# Battery_Management.net
KiCad netlist of a schematic drawn in Altium Designer
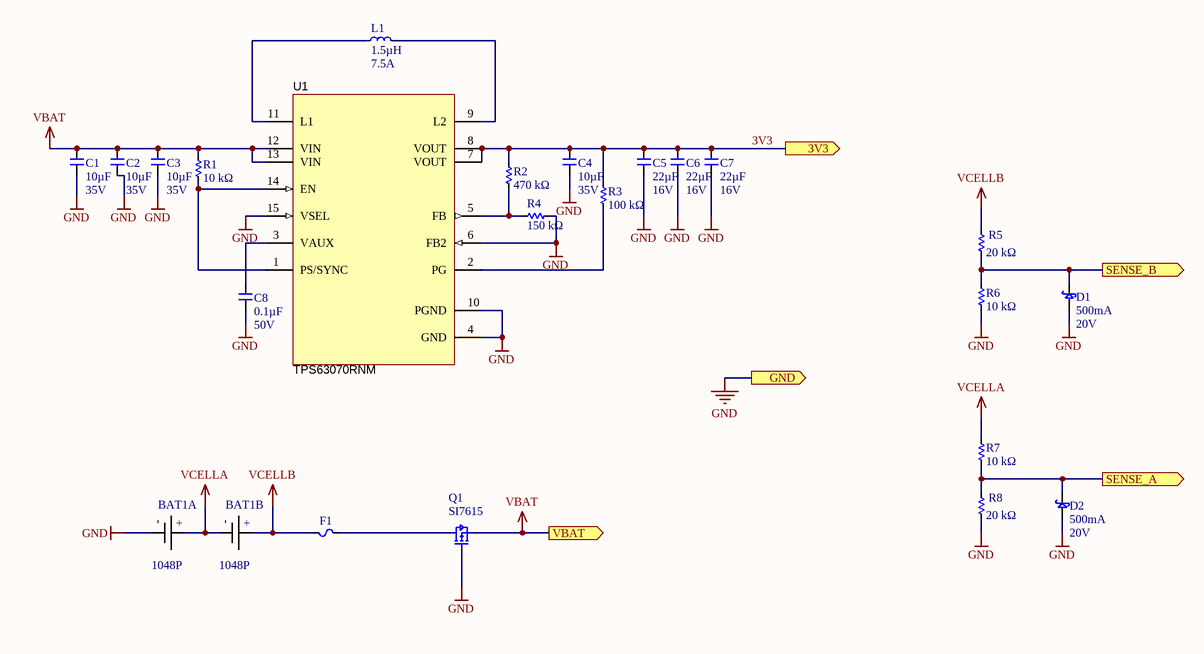
[diagram p0: Battery_Management.SchDoc]

(export (version "E")
  (design (tool "Eeschema 10.0.6"))
  (components
    (comp (ref "BAT1")
      (value "BATT_Clip_Li-Ion_2x")
      (footprint "BATT_18650_KEYSTONE_1048")
      (description "Dual Lithium Ion Cell Holder")
      (fields
        (field (name "MANUFACTURER PART NUMBER") "1048P")
        (field (name "MANUFACTURER") "Keystone Electronics")
      )
      (libsource (lib "Stanford Student Space Initiative") (part "BATT_Clip_Li-Ion_2x"))
    )
    (comp (ref "C1")
      (value "490-13248-1-ND")
      (footprint "C0603")
      (description "CAP CER 10UF 35V X5R 0603 20%")
      (fields
        (field (name "CAPACITANCE (SHORTHAND)") "10µF")
        (field (name "RATED VOLTAGE") "35V")
        (field (name "MANUFACTURER") "Murata Electronics North America")
      )
      (libsource (lib "Stanford Student Space Initiative") (part "__template_cap"))
    )
    (comp (ref "C2")
      (value "490-13248-1-ND")
      (footprint "C0603")
      (description "CAP CER 10UF 35V X5R 0603 20%")
      (fields
        (field (name "CAPACITANCE (SHORTHAND)") "10µF")
        (field (name "RATED VOLTAGE") "35V")
        (field (name "MANUFACTURER") "Murata Electronics North America")
      )
      (libsource (lib "Stanford Student Space Initiative") (part "__template_cap"))
    )
    (comp (ref "C3")
      (value "490-13248-1-ND")
      (footprint "C0603")
      (description "CAP CER 10UF 35V X5R 0603 20%")
      (fields
        (field (name "CAPACITANCE (SHORTHAND)") "10µF")
        (field (name "RATED VOLTAGE") "35V")
        (field (name "MANUFACTURER") "Murata Electronics North America")
      )
      (libsource (lib "Stanford Student Space Initiative") (part "__template_cap"))
    )
    (comp (ref "C4")
      (value "490-13248-1-ND")
      (footprint "C0603")
      (description "CAP CER 10UF 35V X5R 0603 20%")
      (fields
        (field (name "CAPACITANCE (SHORTHAND)") "10µF")
        (field (name "RATED VOLTAGE") "35V")
        (field (name "MANUFACTURER") "Murata Electronics North America")
      )
      (libsource (lib "Stanford Student Space Initiative") (part "__template_cap"))
    )
    (comp (ref "C5")
      (value "1276-7076-1-ND")
      (footprint "C0603")
      (description "CAP CER 22UF 16V X5R 0603 20%")
      (fields
        (field (name "CAPACITANCE (SHORTHAND)") "22µF")
        (field (name "RATED VOLTAGE") "16V")
        (field (name "MANUFACTURER") "Samsung Electro-Mechanics")
      )
      (libsource (lib "Stanford Student Space Initiative") (part "__template_cap"))
    )
    (comp (ref "C6")
      (value "1276-7076-1-ND")
      (footprint "C0603")
      (description "CAP CER 22UF 16V X5R 0603 20%")
      (fields
        (field (name "CAPACITANCE (SHORTHAND)") "22µF")
        (field (name "RATED VOLTAGE") "16V")
        (field (name "MANUFACTURER") "Samsung Electro-Mechanics")
      )
      (libsource (lib "Stanford Student Space Initiative") (part "__template_cap"))
    )
    (comp (ref "C7")
      (value "1276-7076-1-ND")
      (footprint "C0603")
      (description "CAP CER 22UF 16V X5R 0603 20%")
      (fields
        (field (name "CAPACITANCE (SHORTHAND)") "22µF")
        (field (name "RATED VOLTAGE") "16V")
        (field (name "MANUFACTURER") "Samsung Electro-Mechanics")
      )
      (libsource (lib "Stanford Student Space Initiative") (part "__template_cap"))
    )
    (comp (ref "C8")
      (value "490-1519-1-ND")
      (footprint "C0603")
      (description "CAP CER 0603 0.1µF X7R 50V 10%")
      (fields
        (field (name "CAPACITANCE (SHORTHAND)") "0.1µF")
        (field (name "RATED VOLTAGE") "50V")
        (field (name "MANUFACTURER") "Murata Electronics North America")
      )
      (libsource (lib "Stanford Student Space Initiative") (part "__template_cap"))
    )
    (comp (ref "D1")
      (value "SCHOTTKY_MBR0520L")
      (footprint "SOD123")
      (description "DIODE SCHOTTKY 0.5A 20V SOD-123")
      (fields
        (field (name "MANUFACTURER") "Fairchild Semiconductor")
        (field (name "MANUFACTURER PART NUMBER") "MBR0520L")
        (field (name "CURRENT - AVERAGE RECTIFIED (IO)") "500mA")
        (field (name "VOLTAGE - DC REVERSE (VR) (MAX)") "20V")
      )
      (libsource (lib "") (part "Symbol_1"))
    )
    (comp (ref "D2")
      (value "SCHOTTKY_MBR0520L")
      (footprint "SOD123")
      (description "DIODE SCHOTTKY 0.5A 20V SOD-123")
      (fields
        (field (name "MANUFACTURER") "Fairchild Semiconductor")
        (field (name "MANUFACTURER PART NUMBER") "MBR0520L")
        (field (name "CURRENT - AVERAGE RECTIFIED (IO)") "500mA")
        (field (name "VOLTAGE - DC REVERSE (VR) (MAX)") "20V")
      )
      (libsource (lib "") (part "Symbol_1"))
    )
    (comp (ref "F1") (value "__template_fuse") (footprint "R1206") (libsource (lib "") (part "Symbol_2")))
    (comp (ref "L1")
      (value "Symbol")
      (footprint "SMD5230")
      (description "INDUCTOR POWER 1.5UH 7.5A SMD")
      (fields
        (field (name "MANUFACTURER") "Vishay Dale")
        (field (name "MANUFACTURER PART NUMBER") "IHLP2020CZER1R5M11")
        (field (name "INDUCTANCE") "1.5µH")
        (field (name "CURRENT RATING") "7.5A")
      )
      (libsource (lib "Stanford Student Space Initiative") (part "Symbol"))
    )
    (comp (ref "Q1")
      (value "SI7615")
      (footprint "POWERPAK_1212-8_SINGLE")
      (description "MOSFET P-CH 20V 35A PPK")
      (fields
        (field (name "MANUFACTURER") "Vishay Siliconix")
        (field (name "MANUFACTURER PART NUMBER") "SI7615ADN-T1-GE3")
      )
      (libsource (lib "Stanford Student Space Initiative") (part "PFET_SI7615ADN-T1"))
    )
    (comp (ref "R1")
      (value "311-10.0KHRCT-ND")
      (footprint "R0603")
      (description "RES SMD 10K OHM 1% 1/10W 0603")
      (fields
        (field (name "RESISTANCE") "10 kΩ")
        (field (name "MANUFACTURER PART NUMBER") "RC0603FR-0710KL")
        (field (name "MANUFACTURER") "Yageo")
      )
      (libsource (lib "Stanford Student Space Initiative") (part "__template_resistor"))
    )
    (comp (ref "R2")
      (value "311-470KHRCT-ND")
      (footprint "R0603")
      (description "RES SMD 470K OHM 1% 1/10W 0603")
      (fields
        (field (name "MANUFACTURER PART NUMBER") "RC0603FR-07470KL")
        (field (name "MANUFACTURER") "Yageo")
        (field (name "RESISTANCE") "470 kΩ")
      )
      (libsource (lib "Stanford Student Space Initiative") (part "__template_resistor"))
    )
    (comp (ref "R3")
      (value "311-100KHRCT-ND")
      (footprint "R0603")
      (description "RES SMD 100K OHM 1% 1/10W 0603")
      (fields
        (field (name "MANUFACTURER PART NUMBER") "RC0603FR-07100KL")
        (field (name "MANUFACTURER") "Yageo")
        (field (name "RESISTANCE") "100 kΩ")
      )
      (libsource (lib "Stanford Student Space Initiative") (part "__template_resistor"))
    )
    (comp (ref "R4")
      (value "311-150KHRCT-ND")
      (footprint "R0603")
      (description "RES SMD 150K OHM 1% 1/10W 0603")
      (fields
        (field (name "MANUFACTURER PART NUMBER") "RC0603FR-07150KL")
        (field (name "MANUFACTURER") "Yageo")
        (field (name "RESISTANCE") "150 kΩ")
      )
      (libsource (lib "Stanford Student Space Initiative") (part "__template_resistor"))
    )
    (comp (ref "R5")
      (value "311-20.0KHRCT-ND")
      (footprint "R0603")
      (description "RES SMD 20K OHM 1% 1/10W 0603")
      (fields
        (field (name "RESISTANCE") "20 kΩ")
        (field (name "MANUFACTURER PART NUMBER") "RC0603FR-0720KL")
        (field (name "MANUFACTURER") "Yageo")
      )
      (libsource (lib "Stanford Student Space Initiative") (part "__template_resistor"))
    )
    (comp (ref "R6")
      (value "311-10.0KHRCT-ND")
      (footprint "R0603")
      (description "RES SMD 10K OHM 1% 1/10W 0603")
      (fields
        (field (name "RESISTANCE") "10 kΩ")
        (field (name "MANUFACTURER PART NUMBER") "RC0603FR-0710KL")
        (field (name "MANUFACTURER") "Yageo")
      )
      (libsource (lib "Stanford Student Space Initiative") (part "__template_resistor"))
    )
    (comp (ref "R7")
      (value "311-10.0KHRCT-ND")
      (footprint "R0603")
      (description "RES SMD 10K OHM 1% 1/10W 0603")
      (fields
        (field (name "RESISTANCE") "10 kΩ")
        (field (name "MANUFACTURER PART NUMBER") "RC0603FR-0710KL")
        (field (name "MANUFACTURER") "Yageo")
      )
      (libsource (lib "Stanford Student Space Initiative") (part "__template_resistor"))
    )
    (comp (ref "R8")
      (value "311-20.0KHRCT-ND")
      (footprint "R0603")
      (description "RES SMD 20K OHM 1% 1/10W 0603")
      (fields
        (field (name "RESISTANCE") "20 kΩ")
        (field (name "MANUFACTURER PART NUMBER") "RC0603FR-0720KL")
        (field (name "MANUFACTURER") "Yageo")
      )
      (libsource (lib "Stanford Student Space Initiative") (part "__template_resistor"))
    )
    (comp (ref "U1")
      (value "TPS63070RNM")
      (footprint "TPS63070")
      (description "BUCKBOOST TPS63070RNM, RNM0015A")
      (fields
        (field (name "MANUFACTURER") "Texas Instruments")
        (field (name "MANUFACTURER PART NUMBER") "TPS63070RNMR")
      )
      (libsource (lib "Stanford Student Space Initiative") (part "TPS63070RNM"))
    )
  )
  (nets
    (net (code "1") (name "/3V3") (class "Default")
      (node (ref "C4") (pin "1") (pintype "passive"))
      (node (ref "C5") (pin "1") (pintype "passive"))
      (node (ref "C6") (pin "1") (pintype "passive"))
      (node (ref "C7") (pin "1") (pintype "passive"))
      (node (ref "R2") (pin "2") (pinfunction "2_2") (pintype "passive"))
      (node (ref "R3") (pin "2") (pinfunction "2_2") (pintype "passive"))
      (node (ref "U1") (pin "7") (pinfunction "VOUT_7") (pintype "power_in"))
      (node (ref "U1") (pin "8") (pinfunction "VOUT_8") (pintype "power_in"))
    )
    (net (code "2") (name "/SENSE_A") (class "Default")
      (node (ref "D2") (pin "2") (pintype "passive"))
      (node (ref "R7") (pin "1") (pinfunction "1_1") (pintype "passive"))
      (node (ref "R8") (pin "2") (pinfunction "2_2") (pintype "passive"))
    )
    (net (code "3") (name "/SENSE_B") (class "Default")
      (node (ref "D1") (pin "2") (pintype "passive"))
      (node (ref "R5") (pin "1") (pinfunction "1_1") (pintype "passive"))
      (node (ref "R6") (pin "2") (pinfunction "2_2") (pintype "passive"))
    )
    (net (code "4") (name "GND") (class "Default")
      (node (ref "BAT1") (pin "CELL1-") (pinfunction "CELL1-_CELL1-") (pintype "passive"))
      (node (ref "C1") (pin "2") (pintype "passive"))
      (node (ref "C2") (pin "2") (pintype "passive"))
      (node (ref "C3") (pin "2") (pintype "passive"))
      (node (ref "C4") (pin "2") (pintype "passive"))
      (node (ref "C5") (pin "2") (pintype "passive"))
      (node (ref "C6") (pin "2") (pintype "passive"))
      (node (ref "C7") (pin "2") (pintype "passive"))
      (node (ref "C8") (pin "2") (pintype "passive"))
      (node (ref "D1") (pin "1") (pintype "passive"))
      (node (ref "D2") (pin "1") (pintype "passive"))
      (node (ref "Q1") (pin "4") (pintype "passive"))
      (node (ref "R4") (pin "2") (pinfunction "2_2") (pintype "passive"))
      (node (ref "R6") (pin "1") (pinfunction "1_1") (pintype "passive"))
      (node (ref "R8") (pin "1") (pinfunction "1_1") (pintype "passive"))
      (node (ref "U1") (pin "10") (pinfunction "PGND_10") (pintype "power_in"))
      (node (ref "U1") (pin "15") (pinfunction "VSEL_15") (pintype "input"))
      (node (ref "U1") (pin "4") (pinfunction "GND_4") (pintype "power_in"))
      (node (ref "U1") (pin "6") (pinfunction "FB2_6") (pintype "input"))
    )
    (net (code "5") (name "Net-(F1-Pad2)") (class "Default")
      (node (ref "F1") (pin "2") (pintype "passive"))
      (node (ref "Q1") (pin "5") (pintype "passive"))
    )
    (net (code "6") (name "Net-(U1-EN)") (class "Default")
      (node (ref "R1") (pin "1") (pinfunction "1_1") (pintype "passive"))
      (node (ref "U1") (pin "1") (pinfunction "PS/SYNC_1") (pintype "passive"))
      (node (ref "U1") (pin "14") (pinfunction "EN_14") (pintype "input"))
    )
    (net (code "7") (name "Net-(U1-FB)") (class "Default")
      (node (ref "R2") (pin "1") (pinfunction "1_1") (pintype "passive"))
      (node (ref "R4") (pin "1") (pinfunction "1_1") (pintype "passive"))
      (node (ref "U1") (pin "5") (pinfunction "FB_5") (pintype "output"))
    )
    (net (code "8") (name "Net-(U1-L1)") (class "Default")
      (node (ref "L1") (pin "1") (pintype "passive"))
      (node (ref "U1") (pin "11") (pinfunction "L1_11") (pintype "passive"))
    )
    (net (code "9") (name "Net-(U1-L2)") (class "Default")
      (node (ref "L1") (pin "2") (pintype "passive"))
      (node (ref "U1") (pin "9") (pinfunction "L2_9") (pintype "passive"))
    )
    (net (code "10") (name "Net-(U1-PG)") (class "Default")
      (node (ref "R3") (pin "1") (pinfunction "1_1") (pintype "passive"))
      (node (ref "U1") (pin "2") (pinfunction "PG_2") (pintype "open_collector"))
    )
    (net (code "11") (name "Net-(U1-VAUX)") (class "Default")
      (node (ref "C8") (pin "1") (pintype "passive"))
      (node (ref "U1") (pin "3") (pinfunction "VAUX_3") (pintype "passive"))
    )
    (net (code "12") (name "VBAT") (class "Default")
      (node (ref "C1") (pin "1") (pintype "passive"))
      (node (ref "C2") (pin "1") (pintype "passive"))
      (node (ref "C3") (pin "1") (pintype "passive"))
      (node (ref "Q1") (pin "1") (pintype "passive"))
      (node (ref "R1") (pin "2") (pinfunction "2_2") (pintype "passive"))
      (node (ref "U1") (pin "12") (pinfunction "VIN_12") (pintype "power_in"))
      (node (ref "U1") (pin "13") (pinfunction "VIN_13") (pintype "power_in"))
    )
    (net (code "13") (name "VCELLA") (class "Default")
      (node (ref "BAT1") (pin "CELL1+") (pinfunction "CELL1+_CELL1+") (pintype "passive"))
      (node (ref "BAT1") (pin "CELL2-") (pinfunction "CELL2-_CELL2-") (pintype "passive"))
      (node (ref "R7") (pin "2") (pinfunction "2_2") (pintype "passive"))
    )
    (net (code "14") (name "VCELLB") (class "Default")
      (node (ref "BAT1") (pin "CELL2+") (pinfunction "CELL2+_CELL2+") (pintype "passive"))
      (node (ref "F1") (pin "1") (pintype "passive"))
      (node (ref "R5") (pin "2") (pinfunction "2_2") (pintype "passive"))
    )
  )
)
